# PortBreakoutCapacitive_r3.net
KiCad netlist of a schematic drawn in EAGLE
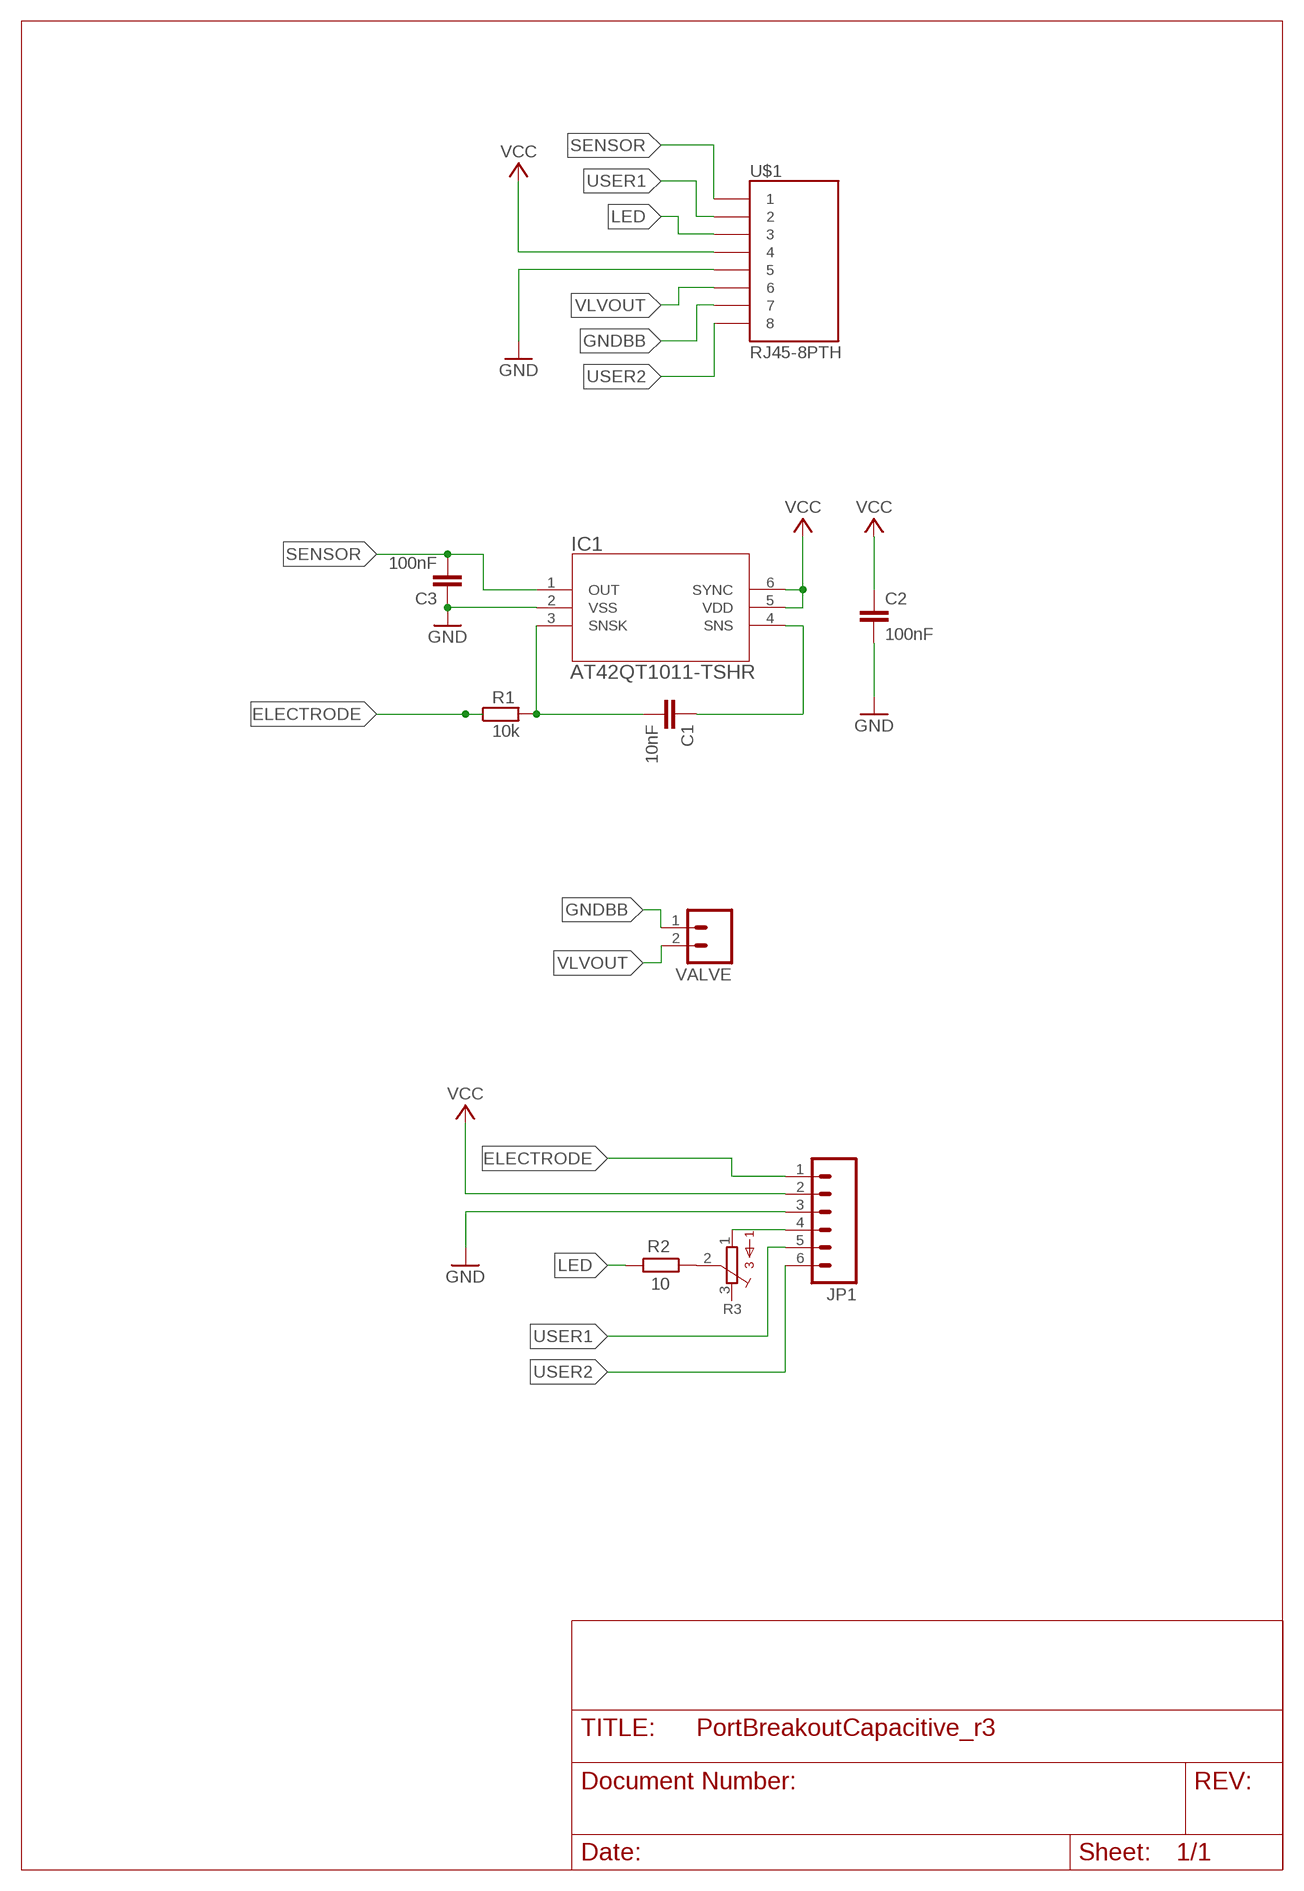
[diagram p0: schematic, sheet 1]

(export (version "E")
  (design (tool "Eeschema 10.0.6"))
  (components
    (comp (ref "C1")
      (value "10nF")
      (footprint "eagle-import:C1206")
      (libsource (lib "eagle-import") (part "C-EUC1206"))
    )
    (comp (ref "C2")
      (value "100nF")
      (footprint "eagle-import:C1206")
      (libsource (lib "eagle-import") (part "C-EUC1206"))
    )
    (comp (ref "C3")
      (value "100nF")
      (footprint "eagle-import:C1206")
      (libsource (lib "eagle-import") (part "C-EUC1206"))
    )
    (comp (ref "IC1")
      (value "AT42QT1011-TSHR")
      (footprint "eagle-import:6ST1_ATM")
      (fields (field (name "MANUFACTURER_PART_NUMBER") "AT42QT1010-TSHR"))
      (libsource (lib "eagle-import") (part "AT42QT1010-TSHR"))
    )
    (comp (ref "JP1")
      (value "M063.5MM-6")
      (footprint "eagle-import:SCREWTERMINAL-3.5MM-6")
      (libsource (lib "eagle-import") (part "M063.5MM-6"))
    )
    (comp (ref "R1")
      (value "10k")
      (footprint "eagle-import:R1206")
      (libsource (lib "eagle-import") (part "R-EU_R1206"))
    )
    (comp (ref "R2")
      (value "10")
      (footprint "eagle-import:R1206")
      (libsource (lib "eagle-import") (part "R-EU_R1206"))
    )
    (comp (ref "R3")
      (value "3362R")
      (footprint "eagle-import:3362R")
      (libsource (lib "eagle-import") (part "3362R"))
    )
    (comp (ref "U$1")
      (value "RJ45-8PTH")
      (footprint "eagle-import:RJ45-8")
      (libsource (lib "eagle-import") (part "RJ45-8PTH"))
    )
    (comp (ref "VALVE")
      (value "M023.5MM_LOCK")
      (footprint "eagle-import:SCREWTERMINAL-3.5MM-2_LOCK")
      (libsource (lib "eagle-import") (part "M023.5MM_LOCK"))
    )
  )
  (nets
    (net (code "1") (name "ELECTRODE") (class "Default")
      (node (ref "JP1") (pin "1") (pinfunction "1_1") (pintype "passive"))
      (node (ref "R1") (pin "1") (pinfunction "1_1") (pintype "passive"))
    )
    (net (code "2") (name "GND") (class "Default")
      (node (ref "C2") (pin "2") (pinfunction "2_2") (pintype "passive"))
      (node (ref "C3") (pin "1") (pinfunction "1_1") (pintype "passive"))
      (node (ref "IC1") (pin "2") (pinfunction "VSS_2") (pintype "power_in"))
      (node (ref "JP1") (pin "3") (pinfunction "3_3") (pintype "passive"))
      (node (ref "U$1") (pin "5") (pinfunction "5_5") (pintype "bidirectional"))
    )
    (net (code "3") (name "GNDBB") (class "Default")
      (node (ref "U$1") (pin "7") (pinfunction "7_7") (pintype "bidirectional"))
      (node (ref "VALVE") (pin "1") (pinfunction "1_1") (pintype "passive"))
    )
    (net (code "4") (name "LED") (class "Default")
      (node (ref "R2") (pin "2") (pinfunction "2_2") (pintype "passive"))
      (node (ref "U$1") (pin "3") (pinfunction "3_3") (pintype "bidirectional"))
    )
    (net (code "5") (name "Net-(IC1-SNS)") (class "Default")
      (node (ref "C1") (pin "1") (pinfunction "1_1") (pintype "passive"))
      (node (ref "IC1") (pin "4") (pinfunction "SNS_4") (pintype "bidirectional"))
    )
    (net (code "6") (name "Net-(IC1-SNSK)") (class "Default")
      (node (ref "C1") (pin "2") (pinfunction "2_2") (pintype "passive"))
      (node (ref "IC1") (pin "3") (pinfunction "SNSK_3") (pintype "bidirectional"))
      (node (ref "R1") (pin "2") (pinfunction "2_2") (pintype "passive"))
    )
    (net (code "7") (name "Net-(JP1-Pad4)") (class "Default")
      (node (ref "JP1") (pin "4") (pinfunction "4_4") (pintype "passive"))
      (node (ref "R3") (pin "1") (pinfunction "1_1") (pintype "passive"))
    )
    (net (code "8") (name "Net-(R2-Pad1)") (class "Default")
      (node (ref "R2") (pin "1") (pinfunction "1_1") (pintype "passive"))
      (node (ref "R3") (pin "2") (pinfunction "2_2") (pintype "passive"))
    )
    (net (code "9") (name "SENSOR") (class "Default")
      (node (ref "C3") (pin "2") (pinfunction "2_2") (pintype "passive"))
      (node (ref "IC1") (pin "1") (pinfunction "OUT_1") (pintype "output"))
      (node (ref "U$1") (pin "1") (pinfunction "1_1") (pintype "bidirectional"))
    )
    (net (code "10") (name "USER1") (class "Default")
      (node (ref "JP1") (pin "5") (pinfunction "5_5") (pintype "passive"))
      (node (ref "U$1") (pin "2") (pinfunction "2_2") (pintype "bidirectional"))
    )
    (net (code "11") (name "USER2") (class "Default")
      (node (ref "JP1") (pin "6") (pinfunction "6_6") (pintype "passive"))
      (node (ref "U$1") (pin "8") (pinfunction "8_8") (pintype "bidirectional"))
    )
    (net (code "12") (name "VCC") (class "Default")
      (node (ref "C2") (pin "1") (pinfunction "1_1") (pintype "passive"))
      (node (ref "IC1") (pin "5") (pinfunction "VDD_5") (pintype "power_in"))
      (node (ref "IC1") (pin "6") (pinfunction "SYNC_6") (pintype "input"))
      (node (ref "JP1") (pin "2") (pinfunction "2_2") (pintype "passive"))
      (node (ref "U$1") (pin "4") (pinfunction "4_4") (pintype "bidirectional"))
    )
    (net (code "13") (name "VLVOUT") (class "Default")
      (node (ref "U$1") (pin "6") (pinfunction "6_6") (pintype "bidirectional"))
      (node (ref "VALVE") (pin "2") (pinfunction "2_2") (pintype "passive"))
    )
    (net (code "14") (name "unconnected-(R3-Pad3)") (class "Default")
      (node (ref "R3") (pin "3") (pinfunction "3_3") (pintype "passive"))
    )
  )
)
